# voltage_divider.net
KiCad netlist of a schematic drawn in EAGLE
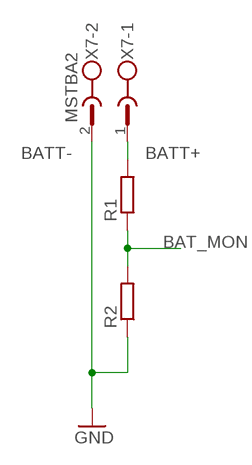
[diagram p0: schematic, sheet 1]

(export (version "E")
  (design (tool "Eeschema 10.0.6"))
  (components
    (comp (ref "R1")
      (value "R-EU_0207/7")
      (footprint "eagle-import:0207_7")
      (libsource (lib "eagle-import") (part "R-EU_0207/7"))
    )
    (comp (ref "R2")
      (value "R-EU_0207/7")
      (footprint "eagle-import:0207_7")
      (libsource (lib "eagle-import") (part "R-EU_0207/7"))
    )
    (comp (ref "X7")
      (value "MSTBA2")
      (footprint "eagle-import:MSTBA2")
      (fields (field (name "MF") "FARNELL") (field (name "MPN") "1757242"))
      (libsource (lib "eagle-import") (part "MSTBA2"))
    )
  )
  (nets
    (net (code "1") (name "/BATT+") (class "Default")
      (node (ref "R1") (pin "2") (pinfunction "2_2") (pintype "passive"))
      (node (ref "X7") (pin "1") (pinfunction "1_1") (pintype "passive"))
    )
    (net (code "2") (name "/BAT_MON") (class "Default")
      (node (ref "R1") (pin "1") (pinfunction "1_1") (pintype "passive"))
      (node (ref "R2") (pin "2") (pinfunction "2_2") (pintype "passive"))
    )
    (net (code "3") (name "GND") (class "Default")
      (node (ref "R2") (pin "1") (pinfunction "1_1") (pintype "passive"))
      (node (ref "X7") (pin "2") (pinfunction "1_2") (pintype "passive"))
    )
  )
)
